# SparkFun_DataLogger_IoT_9DOF.net
KiCad netlist of a schematic drawn in EAGLE
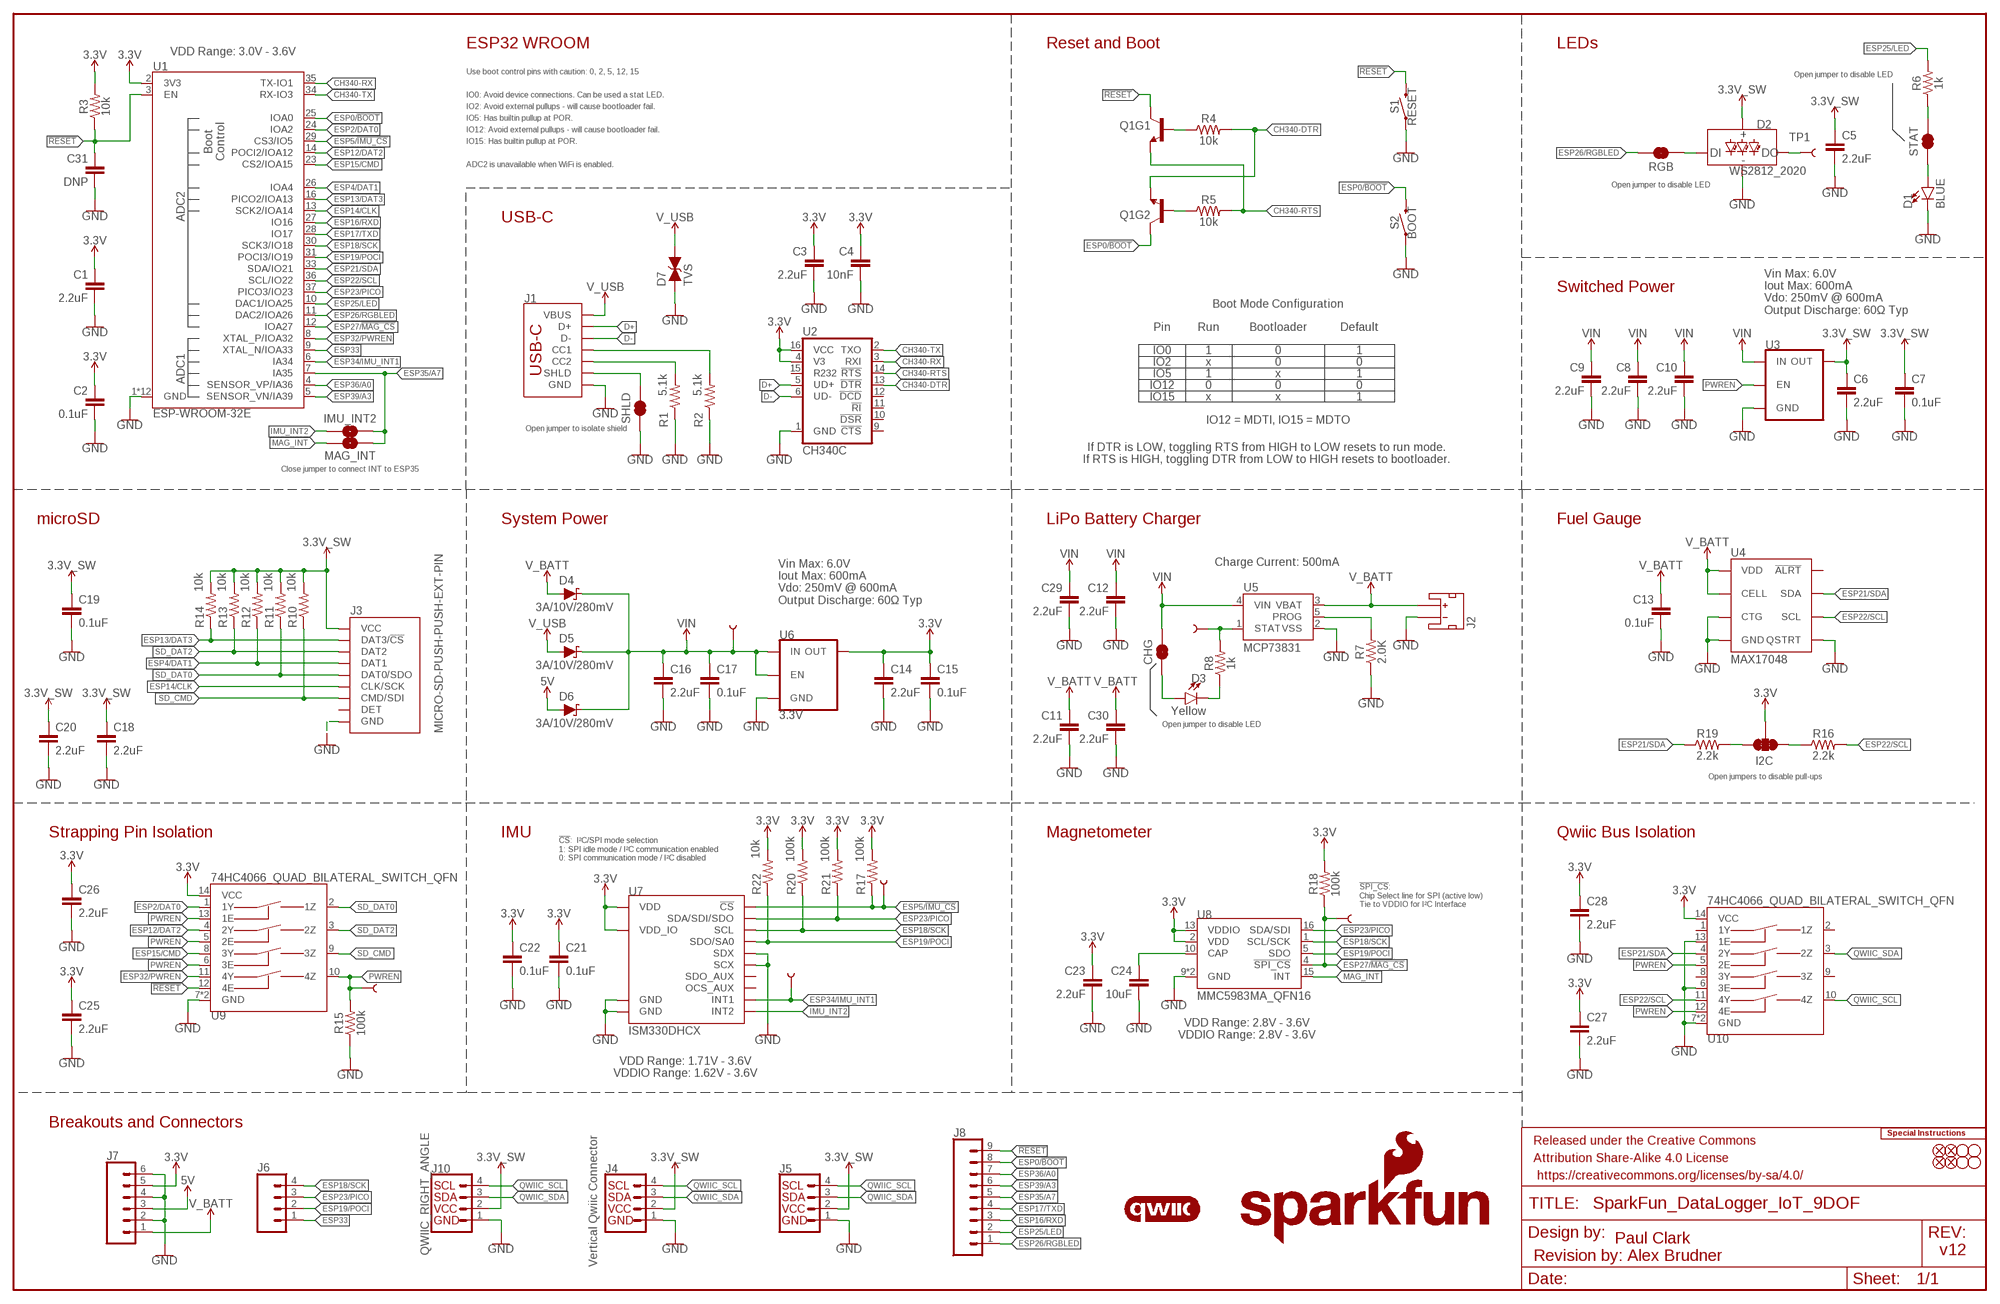
[diagram p0: schematic, sheet 1]

(export (version "E")
  (design (tool "Eeschema 10.0.6"))
  (components
    (comp (ref "C1")
      (value "2.2uF")
      (footprint "eagle-import:0402-TIGHT")
      (libsource (lib "eagle-import") (part "2.2UF-0402_TIGHT-10V-10%-X5R"))
    )
    (comp (ref "C2")
      (value "0.1uF")
      (footprint "eagle-import:0402-TIGHT")
      (libsource (lib "eagle-import") (part "0.1UF-0402T-6.3V-10%-X7R"))
    )
    (comp (ref "C3")
      (value "2.2uF")
      (footprint "eagle-import:0402-TIGHT")
      (libsource (lib "eagle-import") (part "2.2UF-0402_TIGHT-10V-10%-X5R"))
    )
    (comp (ref "C4")
      (value "10nF")
      (footprint "eagle-import:0402-TIGHT")
      (libsource (lib "eagle-import") (part "10NF-0402T-25V-10%-X7R-WE"))
    )
    (comp (ref "C5")
      (value "2.2uF")
      (footprint "eagle-import:0402-TIGHT")
      (libsource (lib "eagle-import") (part "2.2UF-0402_TIGHT-10V-10%-X5R"))
    )
    (comp (ref "C6")
      (value "2.2uF")
      (footprint "eagle-import:0402-TIGHT")
      (libsource (lib "eagle-import") (part "2.2UF-0402_TIGHT-10V-10%-X5R"))
    )
    (comp (ref "C7")
      (value "0.1uF")
      (footprint "eagle-import:0402-TIGHT")
      (libsource (lib "eagle-import") (part "0.1UF-0402T-6.3V-10%-X7R"))
    )
    (comp (ref "C8")
      (value "2.2uF")
      (footprint "eagle-import:0402-TIGHT")
      (libsource (lib "eagle-import") (part "2.2UF-0402_TIGHT-10V-10%-X5R"))
    )
    (comp (ref "C9")
      (value "2.2uF")
      (footprint "eagle-import:0402-TIGHT")
      (libsource (lib "eagle-import") (part "2.2UF-0402_TIGHT-10V-10%-X5R"))
    )
    (comp (ref "C10")
      (value "2.2uF")
      (footprint "eagle-import:0402-TIGHT")
      (libsource (lib "eagle-import") (part "2.2UF-0402_TIGHT-10V-10%-X5R"))
    )
    (comp (ref "C11")
      (value "2.2uF")
      (footprint "eagle-import:0402-TIGHT")
      (libsource (lib "eagle-import") (part "2.2UF-0402_TIGHT-10V-10%-X5R"))
    )
    (comp (ref "C12")
      (value "2.2uF")
      (footprint "eagle-import:0402-TIGHT")
      (libsource (lib "eagle-import") (part "2.2UF-0402_TIGHT-10V-10%-X5R"))
    )
    (comp (ref "C13")
      (value "0.1uF")
      (footprint "eagle-import:0402-TIGHT")
      (libsource (lib "eagle-import") (part "0.1UF-0402T-6.3V-10%-X7R"))
    )
    (comp (ref "C14")
      (value "2.2uF")
      (footprint "eagle-import:0402-TIGHT")
      (libsource (lib "eagle-import") (part "2.2UF-0402_TIGHT-10V-10%-X5R"))
    )
    (comp (ref "C15")
      (value "0.1uF")
      (footprint "eagle-import:0402-TIGHT")
      (libsource (lib "eagle-import") (part "0.1UF-0402T-6.3V-10%-X7R"))
    )
    (comp (ref "C16")
      (value "2.2uF")
      (footprint "eagle-import:0402-TIGHT")
      (libsource (lib "eagle-import") (part "2.2UF-0402_TIGHT-10V-10%-X5R"))
    )
    (comp (ref "C17")
      (value "0.1uF")
      (footprint "eagle-import:0402-TIGHT")
      (libsource (lib "eagle-import") (part "0.1UF-0402T-6.3V-10%-X7R"))
    )
    (comp (ref "C18")
      (value "2.2uF")
      (footprint "eagle-import:0402-TIGHT")
      (libsource (lib "eagle-import") (part "2.2UF-0402_TIGHT-10V-10%-X5R"))
    )
    (comp (ref "C19")
      (value "0.1uF")
      (footprint "eagle-import:0402-TIGHT")
      (libsource (lib "eagle-import") (part "0.1UF-0402T-6.3V-10%-X7R"))
    )
    (comp (ref "C20")
      (value "2.2uF")
      (footprint "eagle-import:0402-TIGHT")
      (libsource (lib "eagle-import") (part "2.2UF-0402_TIGHT-10V-10%-X5R"))
    )
    (comp (ref "C21")
      (value "0.1uF")
      (footprint "eagle-import:0402-TIGHT")
      (libsource (lib "eagle-import") (part "0.1UF-0402T-6.3V-10%-X7R"))
    )
    (comp (ref "C22")
      (value "0.1uF")
      (footprint "eagle-import:0402-TIGHT")
      (libsource (lib "eagle-import") (part "0.1UF-0402T-6.3V-10%-X7R"))
    )
    (comp (ref "C23")
      (value "2.2uF")
      (footprint "eagle-import:0402-TIGHT")
      (libsource (lib "eagle-import") (part "2.2UF-0402_TIGHT-10V-10%-X5R"))
    )
    (comp (ref "C24")
      (value "10uF")
      (footprint "eagle-import:0402-TIGHT")
      (libsource (lib "eagle-import") (part "10UF-0402T-6.3V-20%"))
    )
    (comp (ref "C25")
      (value "2.2uF")
      (footprint "eagle-import:0402-TIGHT")
      (libsource (lib "eagle-import") (part "2.2UF-0402_TIGHT-10V-10%-X5R"))
    )
    (comp (ref "C26")
      (value "2.2uF")
      (footprint "eagle-import:0402-TIGHT")
      (libsource (lib "eagle-import") (part "2.2UF-0402_TIGHT-10V-10%-X5R"))
    )
    (comp (ref "C27")
      (value "2.2uF")
      (footprint "eagle-import:0402-TIGHT")
      (libsource (lib "eagle-import") (part "2.2UF-0402_TIGHT-10V-10%-X5R"))
    )
    (comp (ref "C28")
      (value "2.2uF")
      (footprint "eagle-import:0402-TIGHT")
      (libsource (lib "eagle-import") (part "2.2UF-0402_TIGHT-10V-10%-X5R"))
    )
    (comp (ref "C29")
      (value "2.2uF")
      (footprint "eagle-import:0402-TIGHT")
      (libsource (lib "eagle-import") (part "2.2UF-0402_TIGHT-10V-10%-X5R"))
    )
    (comp (ref "C30")
      (value "2.2uF")
      (footprint "eagle-import:0402-TIGHT")
      (libsource (lib "eagle-import") (part "2.2UF-0402_TIGHT-10V-10%-X5R"))
    )
    (comp (ref "C31")
      (value "DNP")
      (footprint "eagle-import:0402-TIGHT_NO_CREAM")
      (libsource (lib "eagle-import") (part "DNP-0402-TIGHT_NO_CREAM"))
    )
    (comp (ref "CHG")
      (value "JUMPER-SMT_2_NC_TRACE_SILK")
      (footprint "eagle-import:SMT-JUMPER_2_NC_TRACE_SILK")
      (libsource (lib "eagle-import") (part "JUMPER-SMT_2_NC_TRACE_SILK"))
    )
    (comp (ref "D1")
      (value "BLUE")
      (footprint "eagle-import:LED-0603")
      (libsource (lib "eagle-import") (part "LED-BLUE0603"))
    )
    (comp (ref "D2")
      (value "WS2812_2020")
      (footprint "eagle-import:WS2812-2020")
      (libsource (lib "eagle-import") (part "WS2812_2020"))
    )
    (comp (ref "D3")
      (value "Yellow")
      (footprint "eagle-import:LED-0603")
      (libsource (lib "eagle-import") (part "LED-YELLOW0603"))
    )
    (comp (ref "D4")
      (value "3A/10V/280mV")
      (footprint "eagle-import:SOD-323")
      (libsource (lib "eagle-import") (part "DIODE-SCHOTTKY-BAT60A"))
    )
    (comp (ref "D5")
      (value "3A/10V/280mV")
      (footprint "eagle-import:SOD-323")
      (libsource (lib "eagle-import") (part "DIODE-SCHOTTKY-BAT60A"))
    )
    (comp (ref "D6")
      (value "3A/10V/280mV")
      (footprint "eagle-import:SOD-323")
      (libsource (lib "eagle-import") (part "DIODE-SCHOTTKY-BAT60A"))
    )
    (comp (ref "D7")
      (value "TVS")
      (footprint "eagle-import:0603")
      (libsource (lib "eagle-import") (part "DIODE_TVS"))
    )
    (comp (ref "FD1")
      (value "FIDUCIAL1X2")
      (footprint "eagle-import:FIDUCIAL-1X2")
      (libsource (lib "eagle-import") (part "FIDUCIAL1X2"))
    )
    (comp (ref "FD2")
      (value "FIDUCIAL1X2")
      (footprint "eagle-import:FIDUCIAL-1X2")
      (libsource (lib "eagle-import") (part "FIDUCIAL1X2"))
    )
    (comp (ref "FD3")
      (value "FIDUCIAL1X2")
      (footprint "eagle-import:FIDUCIAL-1X2")
      (libsource (lib "eagle-import") (part "FIDUCIAL1X2"))
    )
    (comp (ref "FD4")
      (value "FIDUCIAL1X2")
      (footprint "eagle-import:FIDUCIAL-1X2")
      (libsource (lib "eagle-import") (part "FIDUCIAL1X2"))
    )
    (comp (ref "FRAME1")
      (value "FRAME-LEDGER")
      (footprint "eagle-import:CREATIVE_COMMONS")
      (libsource (lib "eagle-import") (part "FRAME-LEDGER"))
    )
    (comp (ref "H1")
      (value "STAND-OFFTIGHT")
      (footprint "eagle-import:STAND-OFF-TIGHT")
      (libsource (lib "eagle-import") (part "STAND-OFFTIGHT"))
    )
    (comp (ref "H2")
      (value "STAND-OFFTIGHT")
      (footprint "eagle-import:STAND-OFF-TIGHT")
      (libsource (lib "eagle-import") (part "STAND-OFFTIGHT"))
    )
    (comp (ref "H3")
      (value "STAND-OFFTIGHT")
      (footprint "eagle-import:STAND-OFF-TIGHT")
      (libsource (lib "eagle-import") (part "STAND-OFFTIGHT"))
    )
    (comp (ref "H4")
      (value "STAND-OFFTIGHT")
      (footprint "eagle-import:STAND-OFF-TIGHT")
      (libsource (lib "eagle-import") (part "STAND-OFFTIGHT"))
    )
    (comp (ref "I2C")
      (value "JUMPER-SMT_3_2-NC_TRACE_SILK")
      (footprint "eagle-import:SMT-JUMPER_3_2-NC_TRACE_SILK")
      (libsource (lib "eagle-import") (part "JUMPER-SMT_3_2-NC_TRACE_SILK"))
    )
    (comp (ref "IMU_!CS!")
      (value "TEST-POINT3X5")
      (footprint "eagle-import:PAD.03X.05")
      (libsource (lib "eagle-import") (part "TEST-POINT3X5"))
    )
    (comp (ref "IMU_INT1")
      (value "TEST-POINT3X5")
      (footprint "eagle-import:PAD.03X.05")
      (libsource (lib "eagle-import") (part "TEST-POINT3X5"))
    )
    (comp (ref "IMU_INT2")
      (value "JUMPER-SMT_2_NO_SILK")
      (footprint "eagle-import:SMT-JUMPER_2_NO_SILK")
      (libsource (lib "eagle-import") (part "JUMPER-SMT_2_NO_SILK"))
    )
    (comp (ref "J1")
      (value "USB_C_4-LAYER_PADS")
      (footprint "eagle-import:USB-C-16P_4LAYER-PADS")
      (libsource (lib "eagle-import") (part "USB_C_4-LAYER_PADS"))
    )
    (comp (ref "J2")
      (value "JST_2MM_MALE")
      (footprint "eagle-import:JST-2-SMD")
      (libsource (lib "eagle-import") (part "JST_2MM_MALE"))
    )
    (comp (ref "J3")
      (value "MICRO-SD-PUSH-PUSH-EXT-PIN")
      (footprint "eagle-import:MICROSD-EXTERNALPIN")
      (libsource (lib "eagle-import") (part "MICRO-SD-PUSH-PUSH-EXT-PIN"))
    )
    (comp (ref "J4")
      (value "Vertical Qwiic Connector")
      (footprint "eagle-import:JST04_1MM_VERT")
      (libsource (lib "eagle-import") (part "QWIIC_CONNECTOR"))
    )
    (comp (ref "J5")
      (value "I2C_STANDARD_NO_SILK")
      (footprint "eagle-import:1X04_NO_SILK")
      (libsource (lib "eagle-import") (part "I2C_STANDARD_NO_SILK"))
    )
    (comp (ref "J6")
      (value "CONN_041X04_NO_SILK_NO_POP")
      (footprint "eagle-import:1X04_NO_SILK")
      (libsource (lib "eagle-import") (part "CONN_041X04_NO_SILK_NO_POP"))
    )
    (comp (ref "J7")
      (value "CONN_06NO_SILK_NO_POP")
      (footprint "eagle-import:1X06_NO_SILK")
      (libsource (lib "eagle-import") (part "CONN_06NO_SILK_NO_POP"))
    )
    (comp (ref "J8")
      (value "CONN_09NO_SILK")
      (footprint "eagle-import:1X09_NO_SILK")
      (libsource (lib "eagle-import") (part "CONN_09NO_SILK"))
    )
    (comp (ref "J10")
      (value "QWIIC_RIGHT_ANGLE")
      (footprint "eagle-import:JST04_1MM_RA")
      (libsource (lib "eagle-import") (part "QWIIC_CONNECTORJS-1MM"))
    )
    (comp (ref "LOGO1")
      (value "SPECIAL_INSTRUCTIONS-ORDERING")
      (footprint "eagle-import:ORDERING_INSTRUCTIONS")
      (libsource (lib "eagle-import") (part "SPECIAL_INSTRUCTIONS-ORDERING"))
    )
    (comp (ref "LOGO3")
      (value "QWIIC_LOGO_6MM")
      (footprint "eagle-import:QWIIC_6MM")
      (libsource (lib "eagle-import") (part "QWIIC_LOGO_6MM"))
    )
    (comp (ref "LOGO5")
      (value "SFE_LOGO_NAME.2_INCH")
      (footprint "eagle-import:SFE_LOGO_NAME_.2")
      (libsource (lib "eagle-import") (part "SFE_LOGO_NAME.2_INCH"))
    )
    (comp (ref "LOGO6")
      (value "SFE_LOGO_FLAME.2_INCH")
      (footprint "eagle-import:SFE_LOGO_FLAME_.2")
      (libsource (lib "eagle-import") (part "SFE_LOGO_FLAME.2_INCH"))
    )
    (comp (ref "MAG_!CS!")
      (value "TEST-POINT3X5")
      (footprint "eagle-import:PAD.03X.05")
      (libsource (lib "eagle-import") (part "TEST-POINT3X5"))
    )
    (comp (ref "MAG_INT")
      (value "JUMPER-SMT_2_NO_SILK")
      (footprint "eagle-import:SMT-JUMPER_2_NO_SILK")
      (libsource (lib "eagle-import") (part "JUMPER-SMT_2_NO_SILK"))
    )
    (comp (ref "PWREN")
      (value "TEST-POINT3X5")
      (footprint "eagle-import:PAD.03X.05")
      (libsource (lib "eagle-import") (part "TEST-POINT3X5"))
    )
    (comp (ref "Q1")
      (value "TRANS_NPN_DUAL-MBT3904DW1T1")
      (footprint "eagle-import:SC70-6")
      (libsource (lib "eagle-import") (part "TRANS_NPN_DUAL-MBT3904DW1T1"))
    )
    (comp (ref "R1")
      (value "5.1k")
      (footprint "eagle-import:0402-TIGHT")
      (libsource (lib "eagle-import") (part "5.1KOHM-0402T-1/16W-1%"))
    )
    (comp (ref "R2")
      (value "5.1k")
      (footprint "eagle-import:0402-TIGHT")
      (libsource (lib "eagle-import") (part "5.1KOHM-0402T-1/16W-1%"))
    )
    (comp (ref "R3")
      (value "10k")
      (footprint "eagle-import:0402-TIGHT")
      (libsource (lib "eagle-import") (part "10KOHM-0402T-1/16W-1%"))
    )
    (comp (ref "R4")
      (value "10k")
      (footprint "eagle-import:0402-TIGHT")
      (libsource (lib "eagle-import") (part "10KOHM-0402T-1/16W-1%"))
    )
    (comp (ref "R5")
      (value "10k")
      (footprint "eagle-import:0402-TIGHT")
      (libsource (lib "eagle-import") (part "10KOHM-0402T-1/16W-1%"))
    )
    (comp (ref "R6")
      (value "1k")
      (footprint "eagle-import:0402-TIGHT")
      (libsource (lib "eagle-import") (part "1KOHM-0402T-1/16W-1%"))
    )
    (comp (ref "R7")
      (value "2.0K")
      (footprint "eagle-import:0402-TIGHT")
      (libsource (lib "eagle-import") (part "2.0KOHM-0402T-1/16W-1%"))
    )
    (comp (ref "R8")
      (value "1k")
      (footprint "eagle-import:0402-TIGHT")
      (libsource (lib "eagle-import") (part "1KOHM-0402T-1/16W-1%"))
    )
    (comp (ref "R10")
      (value "10k")
      (footprint "eagle-import:0402-TIGHT")
      (libsource (lib "eagle-import") (part "10KOHM-0402T-1/16W-1%"))
    )
    (comp (ref "R11")
      (value "10k")
      (footprint "eagle-import:0402-TIGHT")
      (libsource (lib "eagle-import") (part "10KOHM-0402T-1/16W-1%"))
    )
    (comp (ref "R12")
      (value "10k")
      (footprint "eagle-import:0402-TIGHT")
      (libsource (lib "eagle-import") (part "10KOHM-0402T-1/16W-1%"))
    )
    (comp (ref "R13")
      (value "10k")
      (footprint "eagle-import:0402-TIGHT")
      (libsource (lib "eagle-import") (part "10KOHM-0402T-1/16W-1%"))
    )
    (comp (ref "R14")
      (value "10k")
      (footprint "eagle-import:0402-TIGHT")
      (libsource (lib "eagle-import") (part "10KOHM-0402T-1/16W-1%"))
    )
    (comp (ref "R15")
      (value "100k")
      (footprint "eagle-import:0402-TIGHT")
      (libsource (lib "eagle-import") (part "100KOHM-0402T-1/16W-1%"))
    )
    (comp (ref "R16")
      (value "2.2k")
      (footprint "eagle-import:0402-TIGHT")
      (libsource (lib "eagle-import") (part "2.2KOHM-0402T-1/16W-1%"))
    )
    (comp (ref "R17")
      (value "100k")
      (footprint "eagle-import:0402-TIGHT")
      (libsource (lib "eagle-import") (part "100KOHM-0402T-1/16W-1%"))
    )
    (comp (ref "R18")
      (value "100k")
      (footprint "eagle-import:0402-TIGHT")
      (libsource (lib "eagle-import") (part "100KOHM-0402T-1/16W-1%"))
    )
    (comp (ref "R19")
      (value "2.2k")
      (footprint "eagle-import:0402-TIGHT")
      (libsource (lib "eagle-import") (part "2.2KOHM-0402T-1/16W-1%"))
    )
    (comp (ref "R20")
      (value "100k")
      (footprint "eagle-import:0402-TIGHT")
      (libsource (lib "eagle-import") (part "100KOHM-0402T-1/16W-1%"))
    )
    (comp (ref "R21")
      (value "100k")
      (footprint "eagle-import:0402-TIGHT")
      (libsource (lib "eagle-import") (part "100KOHM-0402T-1/16W-1%"))
    )
    (comp (ref "R22")
      (value "10k")
      (footprint "eagle-import:0402-TIGHT")
      (libsource (lib "eagle-import") (part "10KOHM-0402T-1/16W-1%"))
    )
    (comp (ref "RGB")
      (value "JUMPER-SMT_2_NC_TRACE_SILK")
      (footprint "eagle-import:SMT-JUMPER_2_NC_TRACE_SILK")
      (libsource (lib "eagle-import") (part "JUMPER-SMT_2_NC_TRACE_SILK"))
    )
    (comp (ref "S1")
      (value "RESET")
      (footprint "eagle-import:TACTILE_SWITCH_SMD_RIGHT_ANGLE")
      (libsource (lib "eagle-import") (part "MOMENTARY-SWITCH-SPST-SMD-RIGHT-ANGLE"))
    )
    (comp (ref "S2")
      (value "BOOT")
      (footprint "eagle-import:TACTILE_SWITCH_SMD_RIGHT_ANGLE")
      (libsource (lib "eagle-import") (part "MOMENTARY-SWITCH-SPST-SMD-RIGHT-ANGLE"))
    )
    (comp (ref "SHLD")
      (value "JUMPER-SMT_2_NC_TRACE_SILK")
      (footprint "eagle-import:SMT-JUMPER_2_NC_TRACE_SILK")
      (libsource (lib "eagle-import") (part "JUMPER-SMT_2_NC_TRACE_SILK"))
    )
    (comp (ref "STAT")
      (value "JUMPER-SMT_2_NC_TRACE_SILK")
      (footprint "eagle-import:SMT-JUMPER_2_NC_TRACE_SILK")
      (libsource (lib "eagle-import") (part "JUMPER-SMT_2_NC_TRACE_SILK"))
    )
    (comp (ref "TP1")
      (value "TEST-POINT3X5")
      (footprint "eagle-import:PAD.03X.05")
      (libsource (lib "eagle-import") (part "TEST-POINT3X5"))
    )
    (comp (ref "U1")
      (value "ESP-WROOM-32E")
      (footprint "eagle-import:ESP-WROOM-32D-NARROW")
      (libsource (lib "eagle-import") (part "ESP-WROOM-3232D-NARROW"))
    )
    (comp (ref "U2")
      (value "CH340C")
      (footprint "eagle-import:SO016")
      (libsource (lib "eagle-import") (part "CH340C"))
    )
    (comp (ref "U3")
      (value "3.3V")
      (footprint "eagle-import:SOT23-5")
      (libsource (lib "eagle-import") (part "V_REG_AP2112K-3.3V"))
    )
    (comp (ref "U4")
      (value "MAX17048")
      (footprint "eagle-import:DFN-8")
      (libsource (lib "eagle-import") (part "MAX17048DFN8"))
    )
    (comp (ref "U5")
      (value "MCP73831")
      (footprint "eagle-import:SOT23-5")
      (libsource (lib "eagle-import") (part "MCP73831"))
    )
    (comp (ref "U6")
      (value "3.3V")
      (footprint "eagle-import:SOT23-5")
      (libsource (lib "eagle-import") (part "V_REG_AP2112K-3.3V"))
    )
    (comp (ref "U7")
      (value "ISM330DHCX")
      (footprint "eagle-import:LGA-14L")
      (libsource (lib "eagle-import") (part "ISM330DHCX"))
    )
    (comp (ref "U8")
      (value "MMC5983MA_QFN16")
      (footprint "eagle-import:LGA-16-3X3MM-4X4PINS")
      (libsource (lib "eagle-import") (part "MMC5983MA_QFN16"))
    )
    (comp (ref "U9")
      (value "74HC4066_QUAD_BILATERAL_SWITCH_QFN")
      (footprint "eagle-import:14-QFN")
      (libsource (lib "eagle-import") (part "74HC4066_QUAD_BILATERAL_SWITCH_QFN"))
    )
    (comp (ref "U10")
      (value "74HC4066_QUAD_BILATERAL_SWITCH_QFN")
      (footprint "eagle-import:14-QFN")
      (libsource (lib "eagle-import") (part "74HC4066_QUAD_BILATERAL_SWITCH_QFN"))
    )
    (comp (ref "VIN")
      (value "TEST-POINT3X5")
      (footprint "eagle-import:PAD.03X.05")
      (libsource (lib "eagle-import") (part "TEST-POINT3X5"))
    )
    (comp (ref "VIN1")
      (value "TEST-POINT3X5")
      (footprint "eagle-import:PAD.03X.05")
      (libsource (lib "eagle-import") (part "TEST-POINT3X5"))
    )
  )
  (nets
    (net (code "1") (name "/ESP0{slash}~{BOOT}") (class "Default")
      (node (ref "J8") (pin "8") (pinfunction "8_8") (pintype "passive"))
      (node (ref "Q1") (pin "6") (pinfunction "C_6") (pintype "passive"))
      (node (ref "S2") (pin "2") (pinfunction "2_2") (pintype "passive"))
      (node (ref "U1") (pin "25") (pinfunction "IOA0_25") (pintype "bidirectional"))
    )
    (net (code "2") (name "/ESP5{slash}~{IMU_CS}") (class "Default")
      (node (ref "IMU_!CS!") (pin "1") (pinfunction "1_1") (pintype "bidirectional"))
      (node (ref "R17") (pin "1") (pinfunction "1_1") (pintype "passive"))
      (node (ref "U1") (pin "29") (pinfunction "CS3/IO5_29") (pintype "bidirectional"))
      (node (ref "U7") (pin "P12") (pinfunction "~{CS}_P12") (pintype "bidirectional"))
    )
    (net (code "3") (name "/ESP27{slash}~{MAG_CS}") (class "Default")
      (node (ref "MAG_!CS!") (pin "1") (pinfunction "1_1") (pintype "bidirectional"))
      (node (ref "R18") (pin "1") (pinfunction "1_1") (pintype "passive"))
      (node (ref "U1") (pin "12") (pinfunction "IOA27_12") (pintype "bidirectional"))
      (node (ref "U8") (pin "4") (pinfunction "~{SPI_CS}_4") (pintype "input"))
    )
    (net (code "4") (name "/~{RESET}") (class "Default")
      (node (ref "C31") (pin "1") (pinfunction "1_1") (pintype "passive"))
      (node (ref "J8") (pin "9") (pinfunction "9_9") (pintype "passive"))
      (node (ref "Q1") (pin "3") (pinfunction "C_3") (pintype "passive"))
      (node (ref "R3") (pin "1") (pinfunction "1_1") (pintype "passive"))
      (node (ref "S1") (pin "2") (pinfunction "2_2") (pintype "passive"))
      (node (ref "U1") (pin "3") (pinfunction "EN_3") (pintype "bidirectional"))
      (node (ref "U9") (pin "12") (pinfunction "4E_12") (pintype "bidirectional"))
    )
    (net (code "5") (name "3.3V") (class "Default")
      (node (ref "C1") (pin "1") (pinfunction "1_1") (pintype "passive"))
      (node (ref "C14") (pin "1") (pinfunction "1_1") (pintype "passive"))
      (node (ref "C15") (pin "1") (pinfunction "1_1") (pintype "passive"))
      (node (ref "C2") (pin "1") (pinfunction "1_1") (pintype "passive"))
      (node (ref "C21") (pin "1") (pinfunction "1_1") (pintype "passive"))
      (node (ref "C22") (pin "1") (pinfunction "1_1") (pintype "passive"))
      (node (ref "C23") (pin "1") (pinfunction "1_1") (pintype "passive"))
      (node (ref "C25") (pin "1") (pinfunction "1_1") (pintype "passive"))
      (node (ref "C26") (pin "1") (pinfunction "1_1") (pintype "passive"))
      (node (ref "C27") (pin "1") (pinfunction "1_1") (pintype "passive"))
      (node (ref "C28") (pin "1") (pinfunction "1_1") (pintype "passive"))
      (node (ref "C3") (pin "1") (pinfunction "1_1") (pintype "passive"))
      (node (ref "C4") (pin "1") (pinfunction "1_1") (pintype "passive"))
      (node (ref "I2C") (pin "2") (pinfunction "2_2") (pintype "passive"))
      (node (ref "J7") (pin "5") (pinfunction "5_5") (pintype "passive"))
      (node (ref "R17") (pin "2") (pinfunction "2_2") (pintype "passive"))
      (node (ref "R18") (pin "2") (pinfunction "2_2") (pintype "passive"))
      (node (ref "R20") (pin "2") (pinfunction "2_2") (pintype "passive"))
      (node (ref "R21") (pin "2") (pinfunction "2_2") (pintype "passive"))
      (node (ref "R22") (pin "2") (pinfunction "2_2") (pintype "passive"))
      (node (ref "R3") (pin "2") (pinfunction "2_2") (pintype "passive"))
      (node (ref "U1") (pin "2") (pinfunction "3V3_2") (pintype "bidirectional"))
      (node (ref "U10") (pin "14") (pinfunction "VCC_14") (pintype "bidirectional"))
      (node (ref "U2") (pin "16") (pinfunction "VCC_16") (pintype "bidirectional"))
      (node (ref "U2") (pin "4") (pinfunction "V3_4") (pintype "bidirectional"))
      (node (ref "U6") (pin "5") (pinfunction "OUT_5") (pintype "passive"))
      (node (ref "U7") (pin "P5") (pinfunction "VDD_IO_P5") (pintype "power_in"))
      (node (ref "U7") (pin "P8") (pinfunction "VDD_P8") (pintype "power_in"))
      (node (ref "U8") (pin "13") (pinfunction "VDDIO_13") (pintype "power_in"))
      (node (ref "U8") (pin "2") (pinfunction "VDD_2") (pintype "power_in"))
      (node (ref "U9") (pin "14") (pinfunction "VCC_14") (pintype "bidirectional"))
    )
    (net (code "6") (name "3.3V_SW") (class "Default")
      (node (ref "C18") (pin "1") (pinfunction "1_1") (pintype "passive"))
      (node (ref "C19") (pin "1") (pinfunction "1_1") (pintype "passive"))
      (node (ref "C20") (pin "1") (pinfunction "1_1") (pintype "passive"))
      (node (ref "C5") (pin "1") (pinfunction "1_1") (pintype "passive"))
      (node (ref "C6") (pin "1") (pinfunction "1_1") (pintype "passive"))
      (node (ref "C7") (pin "1") (pinfunction "1_1") (pintype "passive"))
      (node (ref "D2") (pin "VCC") (pinfunction "VCC_VCC") (pintype "bidirectional"))
      (node (ref "J10") (pin "2") (pinfunction "2_2") (pintype "power_in"))
      (node (ref "J3") (pin "4") (pinfunction "VCC_4") (pintype "bidirectional"))
      (node (ref "J4") (pin "2") (pinfunction "2_2") (pintype "power_in"))
      (node (ref "J5") (pin "2") (pinfunction "2_2") (pintype "power_in"))
      (node (ref "R10") (pin "2") (pinfunction "2_2") (pintype "passive"))
      (node (ref "R11") (pin "2") (pinfunction "2_2") (pintype "passive"))
      (node (ref "R12") (pin "2") (pinfunction "2_2") (pintype "passive"))
      (node (ref "R13") (pin "2") (pinfunction "2_2") (pintype "passive"))
      (node (ref "R14") (pin "2") (pinfunction "2_2") (pintype "passive"))
      (node (ref "U3") (pin "5") (pinfunction "OUT_5") (pintype "passive"))
    )
    (net (code "7") (name "5V") (class "Default")
      (node (ref "D6") (pin "A") (pinfunction "A_A") (pintype "passive"))
      (node (ref "J7") (pin "3") (pinfunction "3_3") (pintype "passive"))
    )
    (net (code "8") (name "CH340-DTR") (class "Default")
      (node (ref "Q1") (pin "1") (pinfunction "E_1") (pintype "passive"))
      (node (ref "R4") (pin "2") (pinfunction "2_2") (pintype "passive"))
      (node (ref "U2") (pin "13") (pinfunction "~{DTR}_13") (pintype "bidirectional"))
    )
    (net (code "9") (name "CH340-RTS") (class "Default")
      (node (ref "Q1") (pin "4") (pinfunction "E_4") (pintype "passive"))
      (node (ref "R5") (pin "2") (pinfunction "2_2") (pintype "passive"))
      (node (ref "U2") (pin "14") (pinfunction "~{RTS}_14") (pintype "bidirectional"))
    )
    (net (code "10") (name "CH340-RX") (class "Default")
      (node (ref "U1") (pin "35") (pinfunction "TX-IO1_35") (pintype "bidirectional"))
      (node (ref "U2") (pin "3") (pinfunction "RXI_3") (pintype "bidirectional"))
    )
    (net (code "11") (name "CH340-TX") (class "Default")
      (node (ref "U1") (pin "34") (pinfunction "RX-IO3_34") (pintype "bidirectional"))
      (node (ref "U2") (pin "2") (pinfunction "TXO_2") (pintype "bidirectional"))
    )
    (net (code "12") (name "D+") (class "Default")
      (node (ref "J1") (pin "A6") (pinfunction "D+_A6") (pintype "bidirectional"))
      (node (ref "J1") (pin "B6") (pinfunction "D+_B6") (pintype "bidirectional"))
      (node (ref "U2") (pin "5") (pinfunction "UD+_5") (pintype "bidirectional"))
    )
    (net (code "13") (name "D-") (class "Default")
      (node (ref "J1") (pin "A7") (pinfunction "D-_A7") (pintype "bidirectional"))
      (node (ref "J1") (pin "B7") (pinfunction "D-_B7") (pintype "bidirectional"))
      (node (ref "U2") (pin "6") (pinfunction "UD-_6") (pintype "bidirectional"))
    )
    (net (code "14") (name "ESP2{slash}DAT0") (class "Default")
      (node (ref "U1") (pin "24") (pinfunction "IOA2_24") (pintype "bidirectional"))
      (node (ref "U9") (pin "1") (pinfunction "1Y_1") (pintype "bidirectional"))
    )
    (net (code "15") (name "ESP4{slash}DAT1") (class "Default")
      (node (ref "J3") (pin "8") (pinfunction "DAT1_8") (pintype "bidirectional"))
      (node (ref "R12") (pin "1") (pinfunction "1_1") (pintype "passive"))
      (node (ref "U1") (pin "26") (pinfunction "IOA4_26") (pintype "bidirectional"))
    )
    (net (code "16") (name "ESP12{slash}DAT2") (class "Default")
      (node (ref "U1") (pin "14") (pinfunction "POCI2/IOA12_14") (pintype "bidirectional"))
      (node (ref "U9") (pin "4") (pinfunction "2Y_4") (pintype "bidirectional"))
    )
    (net (code "17") (name "ESP13{slash}DAT3") (class "Default")
      (node (ref "J3") (pin "2") (pinfunction "DAT3/~{CS}_2") (pintype "bidirectional"))
      (node (ref "R14") (pin "1") (pinfunction "1_1") (pintype "passive"))
      (node (ref "U1") (pin "16") (pinfunction "PICO2/IOA13_16") (pintype "bidirectional"))
    )
    (net (code "18") (name "ESP14{slash}CLK") (class "Default")
      (node (ref "J3") (pin "5") (pinfunction "CLK/SCK_5") (pintype "bidirectional"))
      (node (ref "U1") (pin "13") (pinfunction "SCK2/IOA14_13") (pintype "bidirectional"))
    )
    (net (code "19") (name "ESP15{slash}CMD") (class "Default")
      (node (ref "U1") (pin "23") (pinfunction "CS2/IOA15_23") (pintype "bidirectional"))
      (node (ref "U9") (pin "8") (pinfunction "3Y_8") (pintype "bidirectional"))
    )
    (net (code "20") (name "ESP16{slash}RXD") (class "Default")
      (node (ref "J8") (pin "3") (pinfunction "3_3") (pintype "passive"))
      (node (ref "U1") (pin "27") (pinfunction "IO16_27") (pintype "bidirectional"))
    )
    (net (code "21") (name "ESP17{slash}TXD") (class "Default")
      (node (ref "J8") (pin "4") (pinfunction "4_4") (pintype "passive"))
      (node (ref "U1") (pin "28") (pinfunction "IO17_28") (pintype "bidirectional"))
    )
    (net (code "22") (name "ESP18{slash}SCK") (class "Default")
      (node (ref "J6") (pin "4") (pinfunction "4_4") (pintype "passive"))
      (node (ref "R20") (pin "1") (pinfunction "1_1") (pintype "passive"))
      (node (ref "U1") (pin "30") (pinfunction "SCK3/IO18_30") (pintype "bidirectional"))
      (node (ref "U7") (pin "P13") (pinfunction "SCL_P13") (pintype "bidirectional"))
      (node (ref "U8") (pin "1") (pinfunction "SCL/SCK_1") (pintype "bidirectional"))
    )
    (net (code "23") (name "ESP19{slash}POCI") (class "Default")
      (node (ref "J6") (pin "2") (pinfunction "2_2") (pintype "passive"))
      (node (ref "R22") (pin "1") (pinfunction "1_1") (pintype "passive"))
      (node (ref "U1") (pin "31") (pinfunction "POCI3/IO19_31") (pintype "bidirectional"))
      (node (ref "U7") (pin "P1") (pinfunction "SDO/SA0_P1") (pintype "bidirectional"))
      (node (ref "U8") (pin "5") (pinfunction "SDO_5") (pintype "output"))
    )
    (net (code "24") (name "ESP21{slash}SDA") (class "Default")
      (node (ref "R19") (pin "1") (pinfunction "1_1") (pintype "passive"))
      (node (ref "U1") (pin "33") (pinfunction "SDA/IO21_33") (pintype "bidirectional"))
      (node (ref "U10") (pin "4") (pinfunction "2Y_4") (pintype "bidirectional"))
      (node (ref "U4") (pin "8") (pinfunction "SDA_8") (pintype "input"))
    )
    (net (code "25") (name "ESP22{slash}SCL") (class "Default")
      (node (ref "R16") (pin "2") (pinfunction "2_2") (pintype "passive"))
      (node (ref "U1") (pin "36") (pinfunction "SCL/IO22_36") (pintype "bidirectional"))
      (node (ref "U10") (pin "11") (pinfunction "4Y_11") (pintype "bidirectional"))
      (node (ref "U4") (pin "7") (pinfunction "SCL_7") (pintype "output"))
    )
    (net (code "26") (name "ESP23{slash}PICO") (class "Default")
      (node (ref "J6") (pin "3") (pinfunction "3_3") (pintype "passive"))
      (node (ref "R21") (pin "1") (pinfunction "1_1") (pintype "passive"))
      (node (ref "U1") (pin "37") (pinfunction "PICO3/IO23_37") (pintype "bidirectional"))
      (node (ref "U7") (pin "P14") (pinfunction "SDA/SDI/SDO_P14") (pintype "bidirectional"))
      (node (ref "U8") (pin "16") (pinfunction "SDA/SDI_16") (pintype "bidirectional"))
    )
    (net (code "27") (name "ESP25{slash}LED") (class "Default")
      (node (ref "J8") (pin "2") (pinfunction "2_2") (pintype "passive"))
      (node (ref "R6") (pin "2") (pinfunction "2_2") (pintype "passive"))
      (node (ref "U1") (pin "10") (pinfunction "DAC1/IOA25_10") (pintype "bidirectional"))
    )
    (net (code "28") (name "ESP26{slash}RGBLED") (class "Default")
      (node (ref "J8") (pin "1") (pinfunction "1_1") (pintype "passive"))
      (node (ref "RGB") (pin "2") (pinfunction "2_2") (pintype "passive"))
      (node (ref "U1") (pin "11") (pinfunction "DAC2/IOA26_11") (pintype "bidirectional"))
    )
    (net (code "29") (name "ESP32{slash}PWREN") (class "Default")
      (node (ref "U1") (pin "8") (pinfunction "XTAL_P/IOA32_8") (pintype "bidirectional"))
      (node (ref "U9") (pin "11") (pinfunction "4Y_11") (pintype "bidirectional"))
    )
    (net (code "30") (name "ESP33") (class "Default")
      (node (ref "J6") (pin "1") (pinfunction "1_1") (pintype "passive"))
      (node (ref "U1") (pin "9") (pinfunction "XTAL_N/IOA33_9") (pintype "bidirectional"))
    )
    (net (code "31") (name "ESP34{slash}IMU_INT1") (class "Default")
      (node (ref "IMU_INT1") (pin "1") (pinfunction "1_1") (pintype "bidirectional"))
      (node (ref "U1") (pin "6") (pinfunction "IA34_6") (pintype "bidirectional"))
      (node (ref "U7") (pin "P4") (pinfunction "INT1_P4") (pintype "bidirectional"))
    )
    (net (code "32") (name "ESP35{slash}A7") (class "Default")
      (node (ref "IMU_INT2") (pin "2") (pinfunction "2_2") (pintype "passive"))
      (node (ref "J8") (pin "5") (pinfunction "5_5") (pintype "passive"))
      (node (ref "MAG_INT") (pin "2") (pinfunction "2_2") (pintype "passive"))
      (node (ref "U1") (pin "7") (pinfunction "IA35_7") (pintype "bidirectional"))
    )
    (net (code "33") (name "ESP36{slash}A0") (class "Default")
      (node (ref "J8") (pin "7") (pinfunction "7_7") (pintype "passive"))
      (node (ref "U1") (pin "4") (pinfunction "SENSOR_VP/IA36_4") (pintype "bidirectional"))
    )
    (net (code "34") (name "ESP39{slash}A3") (class "Default")
      (node (ref "J8") (pin "6") (pinfunction "6_6") (pintype "passive"))
      (node (ref "U1") (pin "5") (pinfunction "SENSOR_VN/IA39_5") (pintype "bidirectional"))
    )
    (net (code "35") (name "GND") (class "Default")
      (node (ref "C1") (pin "2") (pinfunction "2_2") (pintype "passive"))
      (node (ref "C10") (pin "2") (pinfunction "2_2") (pintype "passive"))
      (node (ref "C11") (pin "2") (pinfunction "2_2") (pintype "passive"))
      (node (ref "C12") (pin "2") (pinfunction "2_2") (pintype "passive"))
      (node (ref "C13") (pin "2") (pinfunction "2_2") (pintype "passive"))
      (node (ref "C14") (pin "2") (pinfunction "2_2") (pintype "passive"))
      (node (ref "C15") (pin "2") (pinfunction "2_2") (pintype "passive"))
      (node (ref "C16") (pin "2") (pinfunction "2_2") (pintype "passive"))
      (node (ref "C17") (pin "2") (pinfunction "2_2") (pintype "passive"))
      (node (ref "C18") (pin "2") (pinfunction "2_2") (pintype "passive"))
      (node (ref "C19") (pin "2") (pinfunction "2_2") (pintype "passive"))
      (node (ref "C2") (pin "2") (pinfunction "2_2") (pintype "passive"))
      (node (ref "C20") (pin "2") (pinfunction "2_2") (pintype "passive"))
      (node (ref "C21") (pin "2") (pinfunction "2_2") (pintype "passive"))
      (node (ref "C22") (pin "2") (pinfunction "2_2") (pintype "passive"))
      (node (ref "C23") (pin "2") (pinfunction "2_2") (pintype "passive"))
      (node (ref "C24") (pin "2") (pinfunction "2_2") (pintype "passive"))
      (node (ref "C25") (pin "2") (pinfunction "2_2") (pintype "passive"))
      (node (ref "C26") (pin "2") (pinfunction "2_2") (pintype "passive"))
      (node (ref "C27") (pin "2") (pinfunction "2_2") (pintype "passive"))
      (node (ref "C28") (pin "2") (pinfunction "2_2") (pintype "passive"))
      (node (ref "C29") (pin "2") (pinfunction "2_2") (pintype "passive"))
      (node (ref "C3") (pin "2") (pinfunction "2_2") (pintype "passive"))
      (node (ref "C30") (pin "2") (pinfunction "2_2") (pintype "passive"))
      (node (ref "C31") (pin "2") (pinfunction "2_2") (pintype "passive"))
      (node (ref "C4") (pin "2") (pinfunction "2_2") (pintype "passive"))
      (node (ref "C5") (pin "2") (pinfunction "2_2") (pintype "passive"))
      (node (ref "C6") (pin "2") (pinfunction "2_2") (pintype "passive"))
      (node (ref "C7") (pin "2") (pinfunction "2_2") (pintype "passive"))
      (node (ref "C8") (pin "2") (pinfunction "2_2") (pintype "passive"))
      (node (ref "C9") (pin "2") (pinfunction "2_2") (pintype "passive"))
      (node (ref "D1") (pin "C") (pinfunction "C_C") (pintype "passive"))
      (node (ref "D2") (pin "GND") (pinfunction "GND_GND") (pintype "bidirectional"))
      (node (ref "D7") (pin "1") (pinfunction "A_1") (pintype "passive"))
      (node (ref "J1") (pin "GND") (pinfunction "GND_GND") (pintype "bidirectional"))
      (node (ref "J1") (pin "GND2") (pinfunction "GND_GND2") (pintype "bidirectional"))
      (node (ref "J10") (pin "1") (pinfunction "1_1") (pintype "power_in"))
      (node (ref "J2") (pin "1") (pinfunction "-_1") (pintype "bidirectional"))
      (node (ref "J3") (pin "10") (pinfunction "GND_10") (pintype "bidirectional"))
      (node (ref "J3") (pin "11") (pinfunction "GND_11") (pintype "bidirectional"))
      (node (ref "J3") (pin "12") (pinfunction "GND_12") (pintype "bidirectional"))
      (node (ref "J3") (pin "13") (pinfunction "GND_13") (pintype "bidirectional"))
      (node (ref "J3") (pin "6") (pinfunction "GND_6") (pintype "bidirectional"))
      (node (ref "J4") (pin "1") (pinfunction "1_1") (pintype "power_in"))
      (node (ref "J5") (pin "1") (pinfunction "1_1") (pintype "power_in"))
      (node (ref "J7") (pin "2") (pinfunction "2_2") (pintype "passive"))
      (node (ref "J7") (pin "4") (pinfunction "4_4") (pintype "passive"))
      (node (ref "J7") (pin "6") (pinfunction "6_6") (pintype "passive"))
      (node (ref "R1") (pin "1") (pinfunction "1_1") (pintype "passive"))
      (node (ref "R15") (pin "1") (pinfunction "1_1") (pintype "passive"))
      (node (ref "R2") (pin "1") (pinfunction "1_1") (pintype "passive"))
      (node (ref "R7") (pin "1") (pinfunction "1_1") (pintype "passive"))
      (node (ref "S1") (pin "1") (pinfunction "1_1") (pintype "passive"))
      (node (ref "S2") (pin "1") (pinfunction "1_1") (pintype "passive"))
      (node (ref "SHLD") (pin "1") (pinfunction "1_1") (pintype "passive"))
      (node (ref "U1") (pin "1") (pinfunction "GND_1") (pintype "bidirectional"))
      (node (ref "U1") (pin "15") (pinfunction "GND_15") (pintype "bidirectional"))
      (node (ref "U1") (pin "38") (pinfunction "GND_38") (pintype "bidirectional"))
      (node (ref "U1") (pin "GND1") (pinfunction "GND_GND1") (pintype "bidirectional"))
      (node (ref "U1") (pin "GNDT1") (pinfunction "GND_GNDT1") (pintype "bidirectional"))
      (node (ref "U1") (pin "GNDT2") (pinfunction "GND_GNDT2") (pintype "bidirectional"))
      (node (ref "U1") (pin "GNDT3") (pinfunction "GND_GNDT3") (pintype "bidirectional"))
      (node (ref "U1") (pin "GNDT4") (pinfunction "GND_GNDT4") (pintype "bidirectional"))
      (node (ref "U1") (pin "GNDT5") (pinfunction "GND_GNDT5") (pintype "bidirectional"))
      (node (ref "U1") (pin "GNDT6") (pinfunction "GND_GNDT6") (pintype "bidirectional"))
      (node (ref "U1") (pin "GNDT7") (pinfunction "GND_GNDT7") (pintype "bidirectional"))
      (node (ref "U1") (pin "GNDT8") (pinfunction "GND_GNDT8") (pintype "bidirectional"))
      (node (ref "U10") (pin "13") (pinfunction "1E_13") (pintype "bidirectional"))
      (node (ref "U10") (pin "6") (pinfunction "3E_6") (pintype "bidirectional"))
      (node (ref "U10") (pin "7") (pinfunction "GND_7") (pintype "bidirectional"))
      (node (ref "U10") (pin "EPAD") (pinfunction "GND_EPAD") (pintype "bidirectional"))
      (node (ref "U2") (pin "1") (pinfunction "GND_1") (pintype "bidirectional"))
      (node (ref "U3") (pin "2") (pinfunction "GND_2") (pintype "input"))
      (node (ref "U4") (pin "1") (pinfunction "CTG_1") (pintype "input"))
      (node (ref "U4") (pin "4") (pinfunction "GND_4") (pintype "bidirectional"))
      (node (ref "U4") (pin "6") (pinfunction "QSTRT_6") (pintype "bidirectional"))
      (node (ref "U4") (pin "9") (pinfunction "GND_9") (pintype "bidirectional"))
      (node (ref "U5") (pin "2") (pinfunction "VSS_2") (pintype "power_in"))
      (node (ref "U6") (pin "2") (pinfunction "GND_2") (pintype "input"))
      (node (ref "U7") (pin "P2") (pinfunction "SDX_P2") (pintype "bidirectional"))
      (node (ref "U7") (pin "P3") (pinfunction "SCX_P3") (pintype "bidirectional"))
      (node (ref "U7") (pin "P6") (pinfunction "GND_P6") (pintype "power_in"))
      (node (ref "U7") (pin "P7") (pinfunction "GND_P7") (pintype "power_in"))
      (node (ref "U8") (pin "11") (pinfunction "GND_11") (pintype "power_in"))
      (node (ref "U8") (pin "9") (pinfunction "GND_9") (pintype "power_in"))
      (node (ref "U9") (pin "7") (pinfunction "GND_7") (pintype "bidirectional"))
      (node (ref "U9") (pin "EPAD") (pinfunction "GND_EPAD") (pintype "bidirectional"))
    )
    (net (code "36") (name "IMU_INT2") (class "Default")
      (node (ref "IMU_INT2") (pin "1") (pinfunction "1_1") (pintype "passive"))
      (node (ref "U7") (pin "P9") (pinfunction "INT2_P9") (pintype "bidirectional"))
    )
    (net (code "37") (name "MAG_INT") (class "Default")
      (node (ref "MAG_INT") (pin "1") (pinfunction "1_1") (pintype "passive"))
      (node (ref "U8") (pin "15") (pinfunction "INT_15") (pintype "output"))
    )
    (net (code "38") (name "Net-(CHG-Pad1)") (class "Default")
      (node (ref "CHG") (pin "1") (pinfunction "1_1") (pintype "passive"))
      (node (ref "D3") (pin "A") (pinfunction "A_A") (pintype "passive"))
    )
    (net (code "39") (name "Net-(D1-PadA)") (class "Default")
      (node (ref "D1") (pin "A") (pinfunction "A_A") (pintype "passive"))
      (node (ref "STAT") (pin "1") (pinfunction "1_1") (pintype "passive"))
    )
    (net (code "40") (name "Net-(D2-PadDI)") (class "Default")
      (node (ref "D2") (pin "DI") (pinfunction "DI_DI") (pintype "bidirectional"))
      (node (ref "RGB") (pin "1") (pinfunction "1_1") (pintype "passive"))
    )
    (net (code "41") (name "Net-(D2-PadDO)") (class "Default")
      (node (ref "D2") (pin "DO") (pinfunction "DO_DO") (pintype "bidirectional"))
      (node (ref "TP1") (pin "1") (pinfunction "1_1") (pintype "bidirectional"))
    )
    (net (code "42") (name "Net-(D3-PadC)") (class "Default")
      (node (ref "D3") (pin "C") (pinfunction "C_C") (pintype "passive"))
      (node (ref "R8") (pin "1") (pinfunction "1_1") (pintype "passive"))
    )
    (net (code "43") (name "Net-(I2C-Pad1)") (class "Default")
      (node (ref "I2C") (pin "1") (pinfunction "1_1") (pintype "passive"))
      (node (ref "R16") (pin "1") (pinfunction "1_1") (pintype "passive"))
    )
    (net (code "44") (name "Net-(I2C-Pad3)") (class "Default")
      (node (ref "I2C") (pin "3") (pinfunction "3_3") (pintype "passive"))
      (node (ref "R19") (pin "2") (pinfunction "2_2") (pintype "passive"))
    )
    (net (code "45") (name "Net-(J1-CC1)") (class "Default")
      (node (ref "J1") (pin "A5") (pinfunction "CC1_A5") (pintype "bidirectional"))
      (node (ref "R2") (pin "2") (pinfunction "2_2") (pintype "passive"))
    )
    (net (code "46") (name "Net-(J1-CC2)") (class "Default")
      (node (ref "J1") (pin "B5") (pinfunction "CC2_B5") (pintype "bidirectional"))
      (node (ref "R1") (pin "2") (pinfunction "2_2") (pintype "passive"))
    )
    (net (code "47") (name "Net-(J1-SHLD-PadSHLD1)") (class "Default")
      (node (ref "J1") (pin "SHLD1") (pinfunction "SHLD_SHLD1") (pintype "bidirectional"))
      (node (ref "J1") (pin "SHLD2") (pinfunction "SHLD_SHLD2") (pintype "bidirectional"))
      (node (ref "J1") (pin "SHLD3") (pinfunction "SHLD_SHLD3") (pintype "bidirectional"))
      (node (ref "J1") (pin "SHLD4") (pinfunction "SHLD_SHLD4") (pintype "bidirectional"))
      (node (ref "SHLD") (pin "2") (pinfunction "2_2") (pintype "passive"))
    )
    (net (code "48") (name "Net-(Q1A-B)") (class "Default")
      (node (ref "Q1") (pin "5") (pinfunction "B_5") (pintype "passive"))
      (node (ref "R4") (pin "1") (pinfunction "1_1") (pintype "passive"))
    )
    (net (code "49") (name "Net-(Q1B-B)") (class "Default")
      (node (ref "Q1") (pin "2") (pinfunction "B_2") (pintype "passive"))
      (node (ref "R5") (pin "1") (pinfunction "1_1") (pintype "passive"))
    )
    (net (code "50") (name "Net-(R6-Pad1)") (class "Default")
      (node (ref "R6") (pin "1") (pinfunction "1_1") (pintype "passive"))
      (node (ref "STAT") (pin "2") (pinfunction "2_2") (pintype "passive"))
    )
    (net (code "51") (name "Net-(U5-PROG)") (class "Default")
      (node (ref "R7") (pin "2") (pinfunction "2_2") (pintype "passive"))
      (node (ref "U5") (pin "5") (pinfunction "PROG_5") (pintype "input"))
    )
    (net (code "52") (name "Net-(U5-STAT)") (class "Default")
      (node (ref "R8") (pin "2") (pinfunction "2_2") (pintype "passive"))
      (node (ref "U5") (pin "1") (pinfunction "STAT_1") (pintype "output"))
      (node (ref "VIN1") (pin "1") (pinfunction "1_1") (pintype "bidirectional"))
    )
    (net (code "53") (name "Net-(U8-CAP)") (class "Default")
      (node (ref "C24") (pin "1") (pinfunction "1_1") (pintype "passive"))
      (node (ref "U8") (pin "10") (pinfunction "CAP_10") (pintype "passive"))
    )
    (net (code "54") (name "PWREN") (class "Default")
      (node (ref "PWREN") (pin "1") (pinfunction "1_1") (pintype "bidirectional"))
      (node (ref "R15") (pin "2") (pinfunction "2_2") (pintype "passive"))
      (node (ref "U10") (pin "12") (pinfunction "4E_12") (pintype "bidirectional"))
      (node (ref "U10") (pin "5") (pinfunction "2E_5") (pintype "bidirectional"))
      (node (ref "U3") (pin "3") (pinfunction "EN_3") (pintype "input"))
      (node (ref "U9") (pin "10") (pinfunction "4Z_10") (pintype "bidirectional"))
      (node (ref "U9") (pin "13") (pinfunction "1E_13") (pintype "bidirectional"))
      (node (ref "U9") (pin "5") (pinfunction "2E_5") (pintype "bidirectional"))
      (node (ref "U9") (pin "6") (pinfunction "3E_6") (pintype "bidirectional"))
    )
    (net (code "55") (name "QWIIC_SCL") (class "Default")
      (node (ref "J10") (pin "4") (pinfunction "4_4") (pintype "passive"))
      (node (ref "J4") (pin "4") (pinfunction "4_4") (pintype "passive"))
      (node (ref "J5") (pin "4") (pinfunction "4_4") (pintype "passive"))
      (node (ref "U10") (pin "10") (pinfunction "4Z_10") (pintype "bidirectional"))
    )
    (net (code "56") (name "QWIIC_SDA") (class "Default")
      (node (ref "J10") (pin "3") (pinfunction "3_3") (pintype "passive"))
      (node (ref "J4") (pin "3") (pinfunction "3_3") (pintype "passive"))
      (node (ref "J5") (pin "3") (pinfunction "3_3") (pintype "passive"))
      (node (ref "U10") (pin "3") (pinfunction "2Z_3") (pintype "bidirectional"))
    )
    (net (code "57") (name "SD_CMD") (class "Default")
      (node (ref "J3") (pin "3") (pinfunction "CMD/SDI_3") (pintype "bidirectional"))
      (node (ref "R10") (pin "1") (pinfunction "1_1") (pintype "passive"))
      (node (ref "U9") (pin "9") (pinfunction "3Z_9") (pintype "bidirectional"))
    )
    (net (code "58") (name "SD_DAT0") (class "Default")
      (node (ref "J3") (pin "7") (pinfunction "DAT0/SDO_7") (pintype "bidirectional"))
      (node (ref "R11") (pin "1") (pinfunction "1_1") (pintype "passive"))
      (node (ref "U9") (pin "2") (pinfunction "1Z_2") (pintype "bidirectional"))
    )
    (net (code "59") (name "SD_DAT2") (class "Default")
      (node (ref "J3") (pin "1") (pinfunction "DAT2_1") (pintype "bidirectional"))
      (node (ref "R13") (pin "1") (pinfunction "1_1") (pintype "passive"))
      (node (ref "U9") (pin "3") (pinfunction "2Z_3") (pintype "bidirectional"))
    )
    (net (code "60") (name "VIN") (class "Default")
      (node (ref "C10") (pin "1") (pinfunction "1_1") (pintype "passive"))
      (node (ref "C12") (pin "1") (pinfunction "1_1") (pintype "passive"))
      (node (ref "C16") (pin "1") (pinfunction "1_1") (pintype "passive"))
      (node (ref "C17") (pin "1") (pinfunction "1_1") (pintype "passive"))
      (node (ref "C29") (pin "1") (pinfunction "1_1") (pintype "passive"))
      (node (ref "C8") (pin "1") (pinfunction "1_1") (pintype "passive"))
      (node (ref "C9") (pin "1") (pinfunction "1_1") (pintype "passive"))
      (node (ref "CHG") (pin "2") (pinfunction "2_2") (pintype "passive"))
      (node (ref "D4") (pin "C") (pinfunction "C_C") (pintype "passive"))
      (node (ref "D5") (pin "C") (pinfunction "C_C") (pintype "passive"))
      (node (ref "D6") (pin "C") (pinfunction "C_C") (pintype "passive"))
      (node (ref "U3") (pin "1") (pinfunction "IN_1") (pintype "input"))
      (node (ref "U5") (pin "4") (pinfunction "VIN_4") (pintype "power_in"))
      (node (ref "U6") (pin "1") (pinfunction "IN_1") (pintype "input"))
      (node (ref "U6") (pin "3") (pinfunction "EN_3") (pintype "input"))
      (node (ref "VIN") (pin "1") (pinfunction "1_1") (pintype "bidirectional"))
    )
    (net (code "61") (name "V_BATT") (class "Default")
      (node (ref "C11") (pin "1") (pinfunction "1_1") (pintype "passive"))
      (node (ref "C13") (pin "1") (pinfunction "1_1") (pintype "passive"))
      (node (ref "C30") (pin "1") (pinfunction "1_1") (pintype "passive"))
      (node (ref "D4") (pin "A") (pinfunction "A_A") (pintype "passive"))
      (node (ref "J2") (pin "2") (pinfunction "+_2") (pintype "bidirectional"))
      (node (ref "J7") (pin "1") (pinfunction "1_1") (pintype "passive"))
      (node (ref "U4") (pin "2") (pinfunction "CELL_2") (pintype "input"))
      (node (ref "U4") (pin "3") (pinfunction "VDD_3") (pintype "bidirectional"))
      (node (ref "U5") (pin "3") (pinfunction "VBAT_3") (pintype "power_in"))
    )
    (net (code "62") (name "V_USB") (class "Default")
      (node (ref "D5") (pin "A") (pinfunction "A_A") (pintype "passive"))
      (node (ref "D7") (pin "2") (pinfunction "C_2") (pintype "passive"))
      (node (ref "J1") (pin "VBUS1") (pinfunction "VBUS_VBUS1") (pintype "bidirectional"))
      (node (ref "J1") (pin "VBUS2") (pinfunction "VBUS_VBUS2") (pintype "bidirectional"))
    )
    (net (code "63") (name "unconnected-(J2-PAD1-PadNC1)") (class "Default")
      (node (ref "J2") (pin "NC1") (pinfunction "PAD1_NC1") (pintype "bidirectional"))
    )
    (net (code "64") (name "unconnected-(J2-PAD2-PadNC2)") (class "Default")
      (node (ref "J2") (pin "NC2") (pinfunction "PAD2_NC2") (pintype "bidirectional"))
    )
    (net (code "65") (name "unconnected-(J3-DET-Pad9)") (class "Default")
      (node (ref "J3") (pin "9") (pinfunction "DET_9") (pintype "bidirectional"))
    )
    (net (code "66") (name "unconnected-(U2-R232-Pad15)") (class "Default")
      (node (ref "U2") (pin "15") (pinfunction "R232_15") (pintype "bidirectional"))
    )
    (net (code "67") (name "unconnected-(U2-~{CTS}-Pad9)") (class "Default")
      (node (ref "U2") (pin "9") (pinfunction "~{CTS}_9") (pintype "bidirectional"))
    )
    (net (code "68") (name "unconnected-(U2-~{DCD}-Pad12)") (class "Default")
      (node (ref "U2") (pin "12") (pinfunction "~{DCD}_12") (pintype "bidirectional"))
    )
    (net (code "69") (name "unconnected-(U2-~{DSR}-Pad10)") (class "Default")
      (node (ref "U2") (pin "10") (pinfunction "~{DSR}_10") (pintype "bidirectional"))
    )
    (net (code "70") (name "unconnected-(U2-~{RI}-Pad11)") (class "Default")
      (node (ref "U2") (pin "11") (pinfunction "~{RI}_11") (pintype "bidirectional"))
    )
    (net (code "71") (name "unconnected-(U4-~{ALRT}-Pad5)") (class "Default")
      (node (ref "U4") (pin "5") (pinfunction "~{ALRT}_5") (pintype "bidirectional"))
    )
    (net (code "72") (name "unconnected-(U7-OCS_AUX-PadP10)") (class "Default")
      (node (ref "U7") (pin "P10") (pinfunction "OCS_AUX_P10") (pintype "bidirectional"))
    )
    (net (code "73") (name "unconnected-(U7-SDO_AUX-PadP11)") (class "Default")
      (node (ref "U7") (pin "P11") (pinfunction "SDO_AUX_P11") (pintype "bidirectional"))
    )
    (net (code "74") (name "unconnected-(U10-1Y-Pad1)") (class "Default")
      (node (ref "U10") (pin "1") (pinfunction "1Y_1") (pintype "bidirectional"))
    )
    (net (code "75") (name "unconnected-(U10-1Z-Pad2)") (class "Default")
      (node (ref "U10") (pin "2") (pinfunction "1Z_2") (pintype "bidirectional"))
    )
    (net (code "76") (name "unconnected-(U10-3Y-Pad8)") (class "Default")
      (node (ref "U10") (pin "8") (pinfunction "3Y_8") (pintype "bidirectional"))
    )
    (net (code "77") (name "unconnected-(U10-3Z-Pad9)") (class "Default")
      (node (ref "U10") (pin "9") (pinfunction "3Z_9") (pintype "bidirectional"))
    )
  )
)
